# Keyswitches.net
KiCad netlist of a schematic drawn in Altium Designer
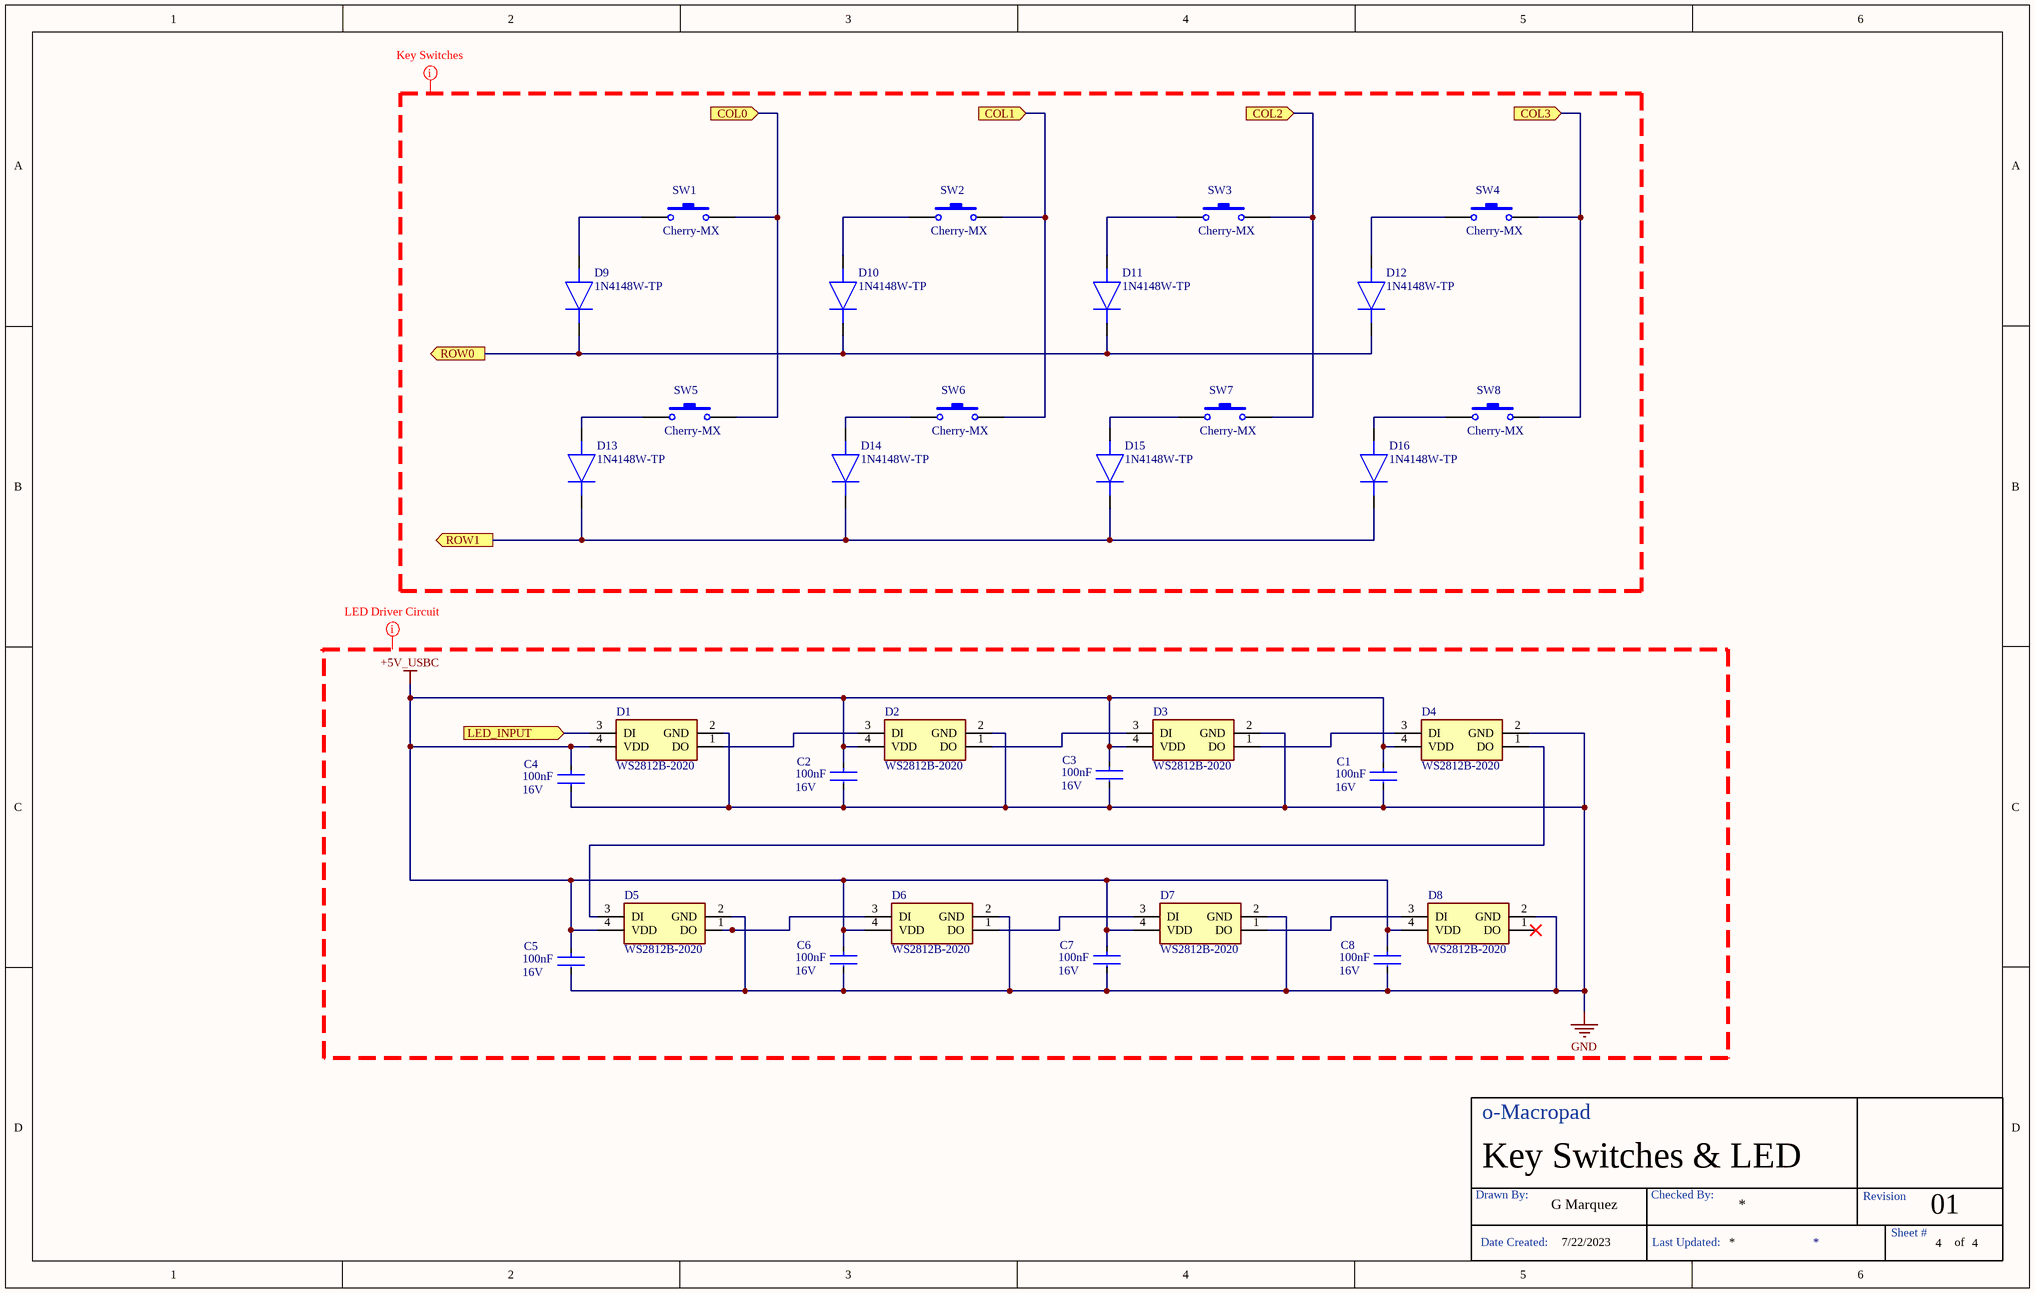
[diagram p0: Keyswitches.SchDoc]

(export (version "E")
  (design (tool "Eeschema 10.0.6"))
  (components
    (comp (ref "C1")
      (value "GRM155R71C104KA88D")
      (footprint "FP-GRM15-MFG")
      (description "CAP CER 0.1UF 16V X7R 0402")
      (fields
        (field (name "TOLERANCE") "10%")
        (field (name "OCTOPART") "https://octopart.com/grm155r71c104ka88d-murata-196880")
        (field (name "VOLTAGE RATING") "16V")
        (field (name "CAPACITANCE") "100nF")
      )
      (libsource (lib "Altium Content Vault") (part "236180d848d6139a670b325ea6854c9"))
    )
    (comp (ref "C2")
      (value "GRM155R71C104KA88D")
      (footprint "FP-GRM15-MFG")
      (description "CAP CER 0.1UF 16V X7R 0402")
      (fields
        (field (name "TOLERANCE") "10%")
        (field (name "OCTOPART") "https://octopart.com/grm155r71c104ka88d-murata-196880")
        (field (name "VOLTAGE RATING") "16V")
        (field (name "CAPACITANCE") "100nF")
      )
      (libsource (lib "Altium Content Vault") (part "236180d848d6139a670b325ea6854c9"))
    )
    (comp (ref "C3")
      (value "GRM155R71C104KA88D")
      (footprint "FP-GRM15-MFG")
      (description "CAP CER 0.1UF 16V X7R 0402")
      (fields
        (field (name "TOLERANCE") "10%")
        (field (name "OCTOPART") "https://octopart.com/grm155r71c104ka88d-murata-196880")
        (field (name "VOLTAGE RATING") "16V")
        (field (name "CAPACITANCE") "100nF")
      )
      (libsource (lib "Altium Content Vault") (part "236180d848d6139a670b325ea6854c9"))
    )
    (comp (ref "C4")
      (value "GRM155R71C104KA88D")
      (footprint "FP-GRM15-MFG")
      (description "CAP CER 0.1UF 16V X7R 0402")
      (fields
        (field (name "TOLERANCE") "10%")
        (field (name "OCTOPART") "https://octopart.com/grm155r71c104ka88d-murata-196880")
        (field (name "VOLTAGE RATING") "16V")
        (field (name "CAPACITANCE") "100nF")
      )
      (libsource (lib "Altium Content Vault") (part "236180d848d6139a670b325ea6854c9"))
    )
    (comp (ref "C5")
      (value "GRM155R71C104KA88D")
      (footprint "FP-GRM15-MFG")
      (description "CAP CER 0.1UF 16V X7R 0402")
      (fields
        (field (name "TOLERANCE") "10%")
        (field (name "OCTOPART") "https://octopart.com/grm155r71c104ka88d-murata-196880")
        (field (name "VOLTAGE RATING") "16V")
        (field (name "CAPACITANCE") "100nF")
      )
      (libsource (lib "Altium Content Vault") (part "236180d848d6139a670b325ea6854c9"))
    )
    (comp (ref "C6")
      (value "GRM155R71C104KA88D")
      (footprint "FP-GRM15-MFG")
      (description "CAP CER 0.1UF 16V X7R 0402")
      (fields
        (field (name "TOLERANCE") "10%")
        (field (name "OCTOPART") "https://octopart.com/grm155r71c104ka88d-murata-196880")
        (field (name "VOLTAGE RATING") "16V")
        (field (name "CAPACITANCE") "100nF")
      )
      (libsource (lib "Altium Content Vault") (part "236180d848d6139a670b325ea6854c9"))
    )
    (comp (ref "C7")
      (value "GRM155R71C104KA88D")
      (footprint "FP-GRM15-MFG")
      (description "CAP CER 0.1UF 16V X7R 0402")
      (fields
        (field (name "TOLERANCE") "10%")
        (field (name "OCTOPART") "https://octopart.com/grm155r71c104ka88d-murata-196880")
        (field (name "VOLTAGE RATING") "16V")
        (field (name "CAPACITANCE") "100nF")
      )
      (libsource (lib "Altium Content Vault") (part "236180d848d6139a670b325ea6854c9"))
    )
    (comp (ref "C8")
      (value "GRM155R71C104KA88D")
      (footprint "FP-GRM15-MFG")
      (description "CAP CER 0.1UF 16V X7R 0402")
      (fields
        (field (name "TOLERANCE") "10%")
        (field (name "OCTOPART") "https://octopart.com/grm155r71c104ka88d-murata-196880")
        (field (name "VOLTAGE RATING") "16V")
        (field (name "CAPACITANCE") "100nF")
      )
      (libsource (lib "Altium Content Vault") (part "236180d848d6139a670b325ea6854c9"))
    )
    (comp (ref "D1")
      (value "WS2812B-2020")
      (footprint "SamacSys:WS2812B2020")
      (description "LED (Multiple)")
      (libsource (lib "*") (part "WS2812B-2020"))
    )
    (comp (ref "D2")
      (value "WS2812B-2020")
      (footprint "SamacSys:WS2812B2020")
      (description "LED (Multiple)")
      (libsource (lib "*") (part "WS2812B-2020"))
    )
    (comp (ref "D3")
      (value "WS2812B-2020")
      (footprint "SamacSys:WS2812B2020")
      (description "LED (Multiple)")
      (libsource (lib "*") (part "WS2812B-2020"))
    )
    (comp (ref "D4")
      (value "WS2812B-2020")
      (footprint "SamacSys:WS2812B2020")
      (description "LED (Multiple)")
      (libsource (lib "*") (part "WS2812B-2020"))
    )
    (comp (ref "D5")
      (value "WS2812B-2020")
      (footprint "SamacSys:WS2812B2020")
      (description "LED (Multiple)")
      (libsource (lib "*") (part "WS2812B-2020"))
    )
    (comp (ref "D6")
      (value "WS2812B-2020")
      (footprint "SamacSys:WS2812B2020")
      (description "LED (Multiple)")
      (libsource (lib "*") (part "WS2812B-2020"))
    )
    (comp (ref "D7")
      (value "WS2812B-2020")
      (footprint "SamacSys:WS2812B2020")
      (description "LED (Multiple)")
      (libsource (lib "*") (part "WS2812B-2020"))
    )
    (comp (ref "D8")
      (value "WS2812B-2020")
      (footprint "SamacSys:WS2812B2020")
      (description "LED (Multiple)")
      (libsource (lib "*") (part "WS2812B-2020"))
    )
    (comp (ref "D9")
      (value "1N4148W-TP")
      (footprint "SamacSys:SOD3715X135N")
      (description "Diode")
      (fields (field (name "MOUSER PART NUMBER") "833-1N4148W-TP"))
      (libsource (lib "*") (part "1N4148W-TP"))
    )
    (comp (ref "D10")
      (value "1N4148W-TP")
      (footprint "SamacSys:SOD3715X135N")
      (description "Diode")
      (fields (field (name "MOUSER PART NUMBER") "833-1N4148W-TP"))
      (libsource (lib "*") (part "1N4148W-TP"))
    )
    (comp (ref "D11")
      (value "1N4148W-TP")
      (footprint "SamacSys:SOD3715X135N")
      (description "Diode")
      (fields (field (name "MOUSER PART NUMBER") "833-1N4148W-TP"))
      (libsource (lib "*") (part "1N4148W-TP"))
    )
    (comp (ref "D12")
      (value "1N4148W-TP")
      (footprint "SamacSys:SOD3715X135N")
      (description "Diode")
      (fields (field (name "MOUSER PART NUMBER") "833-1N4148W-TP"))
      (libsource (lib "*") (part "1N4148W-TP"))
    )
    (comp (ref "D13")
      (value "1N4148W-TP")
      (footprint "SamacSys:SOD3715X135N")
      (description "Diode")
      (fields (field (name "MOUSER PART NUMBER") "833-1N4148W-TP"))
      (libsource (lib "*") (part "1N4148W-TP"))
    )
    (comp (ref "D14")
      (value "1N4148W-TP")
      (footprint "SamacSys:SOD3715X135N")
      (description "Diode")
      (fields (field (name "MOUSER PART NUMBER") "833-1N4148W-TP"))
      (libsource (lib "*") (part "1N4148W-TP"))
    )
    (comp (ref "D15")
      (value "1N4148W-TP")
      (footprint "SamacSys:SOD3715X135N")
      (description "Diode")
      (fields (field (name "MOUSER PART NUMBER") "833-1N4148W-TP"))
      (libsource (lib "*") (part "1N4148W-TP"))
    )
    (comp (ref "D16")
      (value "1N4148W-TP")
      (footprint "SamacSys:SOD3715X135N")
      (description "Diode")
      (fields (field (name "MOUSER PART NUMBER") "833-1N4148W-TP"))
      (libsource (lib "*") (part "1N4148W-TP"))
    )
    (comp (ref "SW1")
      (value "Cherry-MX")
      (footprint "CHERRYMX_1.00U_HOTSWAP_NOSILK")
      (libsource (lib "Macro") (part "Cherry-MX"))
    )
    (comp (ref "SW2")
      (value "Cherry-MX")
      (footprint "CHERRYMX_1.00U_HOTSWAP_NOSILK")
      (libsource (lib "Macro") (part "Cherry-MX"))
    )
    (comp (ref "SW3")
      (value "Cherry-MX")
      (footprint "CHERRYMX_1.00U_HOTSWAP_NOSILK")
      (libsource (lib "Macro") (part "Cherry-MX"))
    )
    (comp (ref "SW4")
      (value "Cherry-MX")
      (footprint "CHERRYMX_1.00U_HOTSWAP_NOSILK")
      (libsource (lib "Macro") (part "Cherry-MX"))
    )
    (comp (ref "SW5")
      (value "Cherry-MX")
      (footprint "CHERRYMX_1.00U_HOTSWAP_NOSILK")
      (libsource (lib "Macro") (part "Cherry-MX"))
    )
    (comp (ref "SW6")
      (value "Cherry-MX")
      (footprint "CHERRYMX_1.00U_HOTSWAP_NOSILK")
      (libsource (lib "Macro") (part "Cherry-MX"))
    )
    (comp (ref "SW7")
      (value "Cherry-MX")
      (footprint "CHERRYMX_1.00U_HOTSWAP_NOSILK")
      (libsource (lib "Macro") (part "Cherry-MX"))
    )
    (comp (ref "SW8")
      (value "Cherry-MX")
      (footprint "CHERRYMX_1.00U_HOTSWAP_NOSILK")
      (libsource (lib "Macro") (part "Cherry-MX"))
    )
  )
  (nets
    (net (code "1") (name "+5V_USBC") (class "Default")
      (node (ref "C1") (pin "2") (pinfunction "2_2") (pintype "passive"))
      (node (ref "C2") (pin "2") (pinfunction "2_2") (pintype "passive"))
      (node (ref "C3") (pin "2") (pinfunction "2_2") (pintype "passive"))
      (node (ref "C4") (pin "2") (pinfunction "2_2") (pintype "passive"))
      (node (ref "C5") (pin "2") (pinfunction "2_2") (pintype "passive"))
      (node (ref "C6") (pin "2") (pinfunction "2_2") (pintype "passive"))
      (node (ref "C7") (pin "2") (pinfunction "2_2") (pintype "passive"))
      (node (ref "C8") (pin "2") (pinfunction "2_2") (pintype "passive"))
      (node (ref "D1") (pin "4") (pinfunction "VDD_4") (pintype "passive"))
      (node (ref "D2") (pin "4") (pinfunction "VDD_4") (pintype "passive"))
      (node (ref "D3") (pin "4") (pinfunction "VDD_4") (pintype "passive"))
      (node (ref "D4") (pin "4") (pinfunction "VDD_4") (pintype "passive"))
      (node (ref "D5") (pin "4") (pinfunction "VDD_4") (pintype "passive"))
      (node (ref "D6") (pin "4") (pinfunction "VDD_4") (pintype "passive"))
      (node (ref "D7") (pin "4") (pinfunction "VDD_4") (pintype "passive"))
      (node (ref "D8") (pin "4") (pinfunction "VDD_4") (pintype "passive"))
    )
    (net (code "2") (name "/COL0") (class "Default")
      (node (ref "SW1") (pin "2") (pinfunction "2_2") (pintype "passive"))
      (node (ref "SW5") (pin "2") (pinfunction "2_2") (pintype "passive"))
    )
    (net (code "3") (name "/COL1") (class "Default")
      (node (ref "SW2") (pin "2") (pinfunction "2_2") (pintype "passive"))
      (node (ref "SW6") (pin "2") (pinfunction "2_2") (pintype "passive"))
    )
    (net (code "4") (name "/COL2") (class "Default")
      (node (ref "SW3") (pin "2") (pinfunction "2_2") (pintype "passive"))
      (node (ref "SW7") (pin "2") (pinfunction "2_2") (pintype "passive"))
    )
    (net (code "5") (name "/COL3") (class "Default")
      (node (ref "SW4") (pin "2") (pinfunction "2_2") (pintype "passive"))
      (node (ref "SW8") (pin "2") (pinfunction "2_2") (pintype "passive"))
    )
    (net (code "6") (name "/LED_INPUT") (class "Default")
      (node (ref "D1") (pin "3") (pinfunction "DI_3") (pintype "passive"))
    )
    (net (code "7") (name "/ROW0") (class "Default")
      (node (ref "D10") (pin "1") (pinfunction "K_1") (pintype "passive"))
      (node (ref "D11") (pin "1") (pinfunction "K_1") (pintype "passive"))
      (node (ref "D12") (pin "1") (pinfunction "K_1") (pintype "passive"))
      (node (ref "D9") (pin "1") (pinfunction "K_1") (pintype "passive"))
    )
    (net (code "8") (name "/ROW1") (class "Default")
      (node (ref "D13") (pin "1") (pinfunction "K_1") (pintype "passive"))
      (node (ref "D14") (pin "1") (pinfunction "K_1") (pintype "passive"))
      (node (ref "D15") (pin "1") (pinfunction "K_1") (pintype "passive"))
      (node (ref "D16") (pin "1") (pinfunction "K_1") (pintype "passive"))
    )
    (net (code "9") (name "GND") (class "Default")
      (node (ref "C1") (pin "1") (pinfunction "1_1") (pintype "passive"))
      (node (ref "C2") (pin "1") (pinfunction "1_1") (pintype "passive"))
      (node (ref "C3") (pin "1") (pinfunction "1_1") (pintype "passive"))
      (node (ref "C4") (pin "1") (pinfunction "1_1") (pintype "passive"))
      (node (ref "C5") (pin "1") (pinfunction "1_1") (pintype "passive"))
      (node (ref "C6") (pin "1") (pinfunction "1_1") (pintype "passive"))
      (node (ref "C7") (pin "1") (pinfunction "1_1") (pintype "passive"))
      (node (ref "C8") (pin "1") (pinfunction "1_1") (pintype "passive"))
      (node (ref "D1") (pin "2") (pinfunction "GND_2") (pintype "passive"))
      (node (ref "D2") (pin "2") (pinfunction "GND_2") (pintype "passive"))
      (node (ref "D3") (pin "2") (pinfunction "GND_2") (pintype "passive"))
      (node (ref "D4") (pin "2") (pinfunction "GND_2") (pintype "passive"))
      (node (ref "D5") (pin "2") (pinfunction "GND_2") (pintype "passive"))
      (node (ref "D6") (pin "2") (pinfunction "GND_2") (pintype "passive"))
      (node (ref "D7") (pin "2") (pinfunction "GND_2") (pintype "passive"))
      (node (ref "D8") (pin "2") (pinfunction "GND_2") (pintype "passive"))
    )
    (net (code "10") (name "Net-(D1-DO)") (class "Default")
      (node (ref "D1") (pin "1") (pinfunction "DO_1") (pintype "passive"))
      (node (ref "D2") (pin "3") (pinfunction "DI_3") (pintype "passive"))
    )
    (net (code "11") (name "Net-(D2-DO)") (class "Default")
      (node (ref "D2") (pin "1") (pinfunction "DO_1") (pintype "passive"))
      (node (ref "D3") (pin "3") (pinfunction "DI_3") (pintype "passive"))
    )
    (net (code "12") (name "Net-(D3-DO)") (class "Default")
      (node (ref "D3") (pin "1") (pinfunction "DO_1") (pintype "passive"))
      (node (ref "D4") (pin "3") (pinfunction "DI_3") (pintype "passive"))
    )
    (net (code "13") (name "Net-(D4-DO)") (class "Default")
      (node (ref "D4") (pin "1") (pinfunction "DO_1") (pintype "passive"))
      (node (ref "D5") (pin "3") (pinfunction "DI_3") (pintype "passive"))
    )
    (net (code "14") (name "Net-(D5-DO)") (class "Default")
      (node (ref "D5") (pin "1") (pinfunction "DO_1") (pintype "passive"))
      (node (ref "D6") (pin "3") (pinfunction "DI_3") (pintype "passive"))
    )
    (net (code "15") (name "Net-(D6-DO)") (class "Default")
      (node (ref "D6") (pin "1") (pinfunction "DO_1") (pintype "passive"))
      (node (ref "D7") (pin "3") (pinfunction "DI_3") (pintype "passive"))
    )
    (net (code "16") (name "Net-(D7-DO)") (class "Default")
      (node (ref "D7") (pin "1") (pinfunction "DO_1") (pintype "passive"))
      (node (ref "D8") (pin "3") (pinfunction "DI_3") (pintype "passive"))
    )
    (net (code "17") (name "Net-(D9-A)") (class "Default")
      (node (ref "D9") (pin "2") (pinfunction "A_2") (pintype "passive"))
      (node (ref "SW1") (pin "1") (pinfunction "1_1") (pintype "passive"))
    )
    (net (code "18") (name "Net-(D10-A)") (class "Default")
      (node (ref "D10") (pin "2") (pinfunction "A_2") (pintype "passive"))
      (node (ref "SW2") (pin "1") (pinfunction "1_1") (pintype "passive"))
    )
    (net (code "19") (name "Net-(D11-A)") (class "Default")
      (node (ref "D11") (pin "2") (pinfunction "A_2") (pintype "passive"))
      (node (ref "SW3") (pin "1") (pinfunction "1_1") (pintype "passive"))
    )
    (net (code "20") (name "Net-(D12-A)") (class "Default")
      (node (ref "D12") (pin "2") (pinfunction "A_2") (pintype "passive"))
      (node (ref "SW4") (pin "1") (pinfunction "1_1") (pintype "passive"))
    )
    (net (code "21") (name "Net-(D13-A)") (class "Default")
      (node (ref "D13") (pin "2") (pinfunction "A_2") (pintype "passive"))
      (node (ref "SW5") (pin "1") (pinfunction "1_1") (pintype "passive"))
    )
    (net (code "22") (name "Net-(D14-A)") (class "Default")
      (node (ref "D14") (pin "2") (pinfunction "A_2") (pintype "passive"))
      (node (ref "SW6") (pin "1") (pinfunction "1_1") (pintype "passive"))
    )
    (net (code "23") (name "Net-(D15-A)") (class "Default")
      (node (ref "D15") (pin "2") (pinfunction "A_2") (pintype "passive"))
      (node (ref "SW7") (pin "1") (pinfunction "1_1") (pintype "passive"))
    )
    (net (code "24") (name "Net-(D16-A)") (class "Default")
      (node (ref "D16") (pin "2") (pinfunction "A_2") (pintype "passive"))
      (node (ref "SW8") (pin "1") (pinfunction "1_1") (pintype "passive"))
    )
    (net (code "25") (name "unconnected-(D8-DO-Pad1)") (class "Default")
      (node (ref "D8") (pin "1") (pinfunction "DO_1") (pintype "passive+no_connect"))
    )
  )
)
